# OSSI-1_LED_Panel.net
KiCad netlist of a schematic drawn in EAGLE
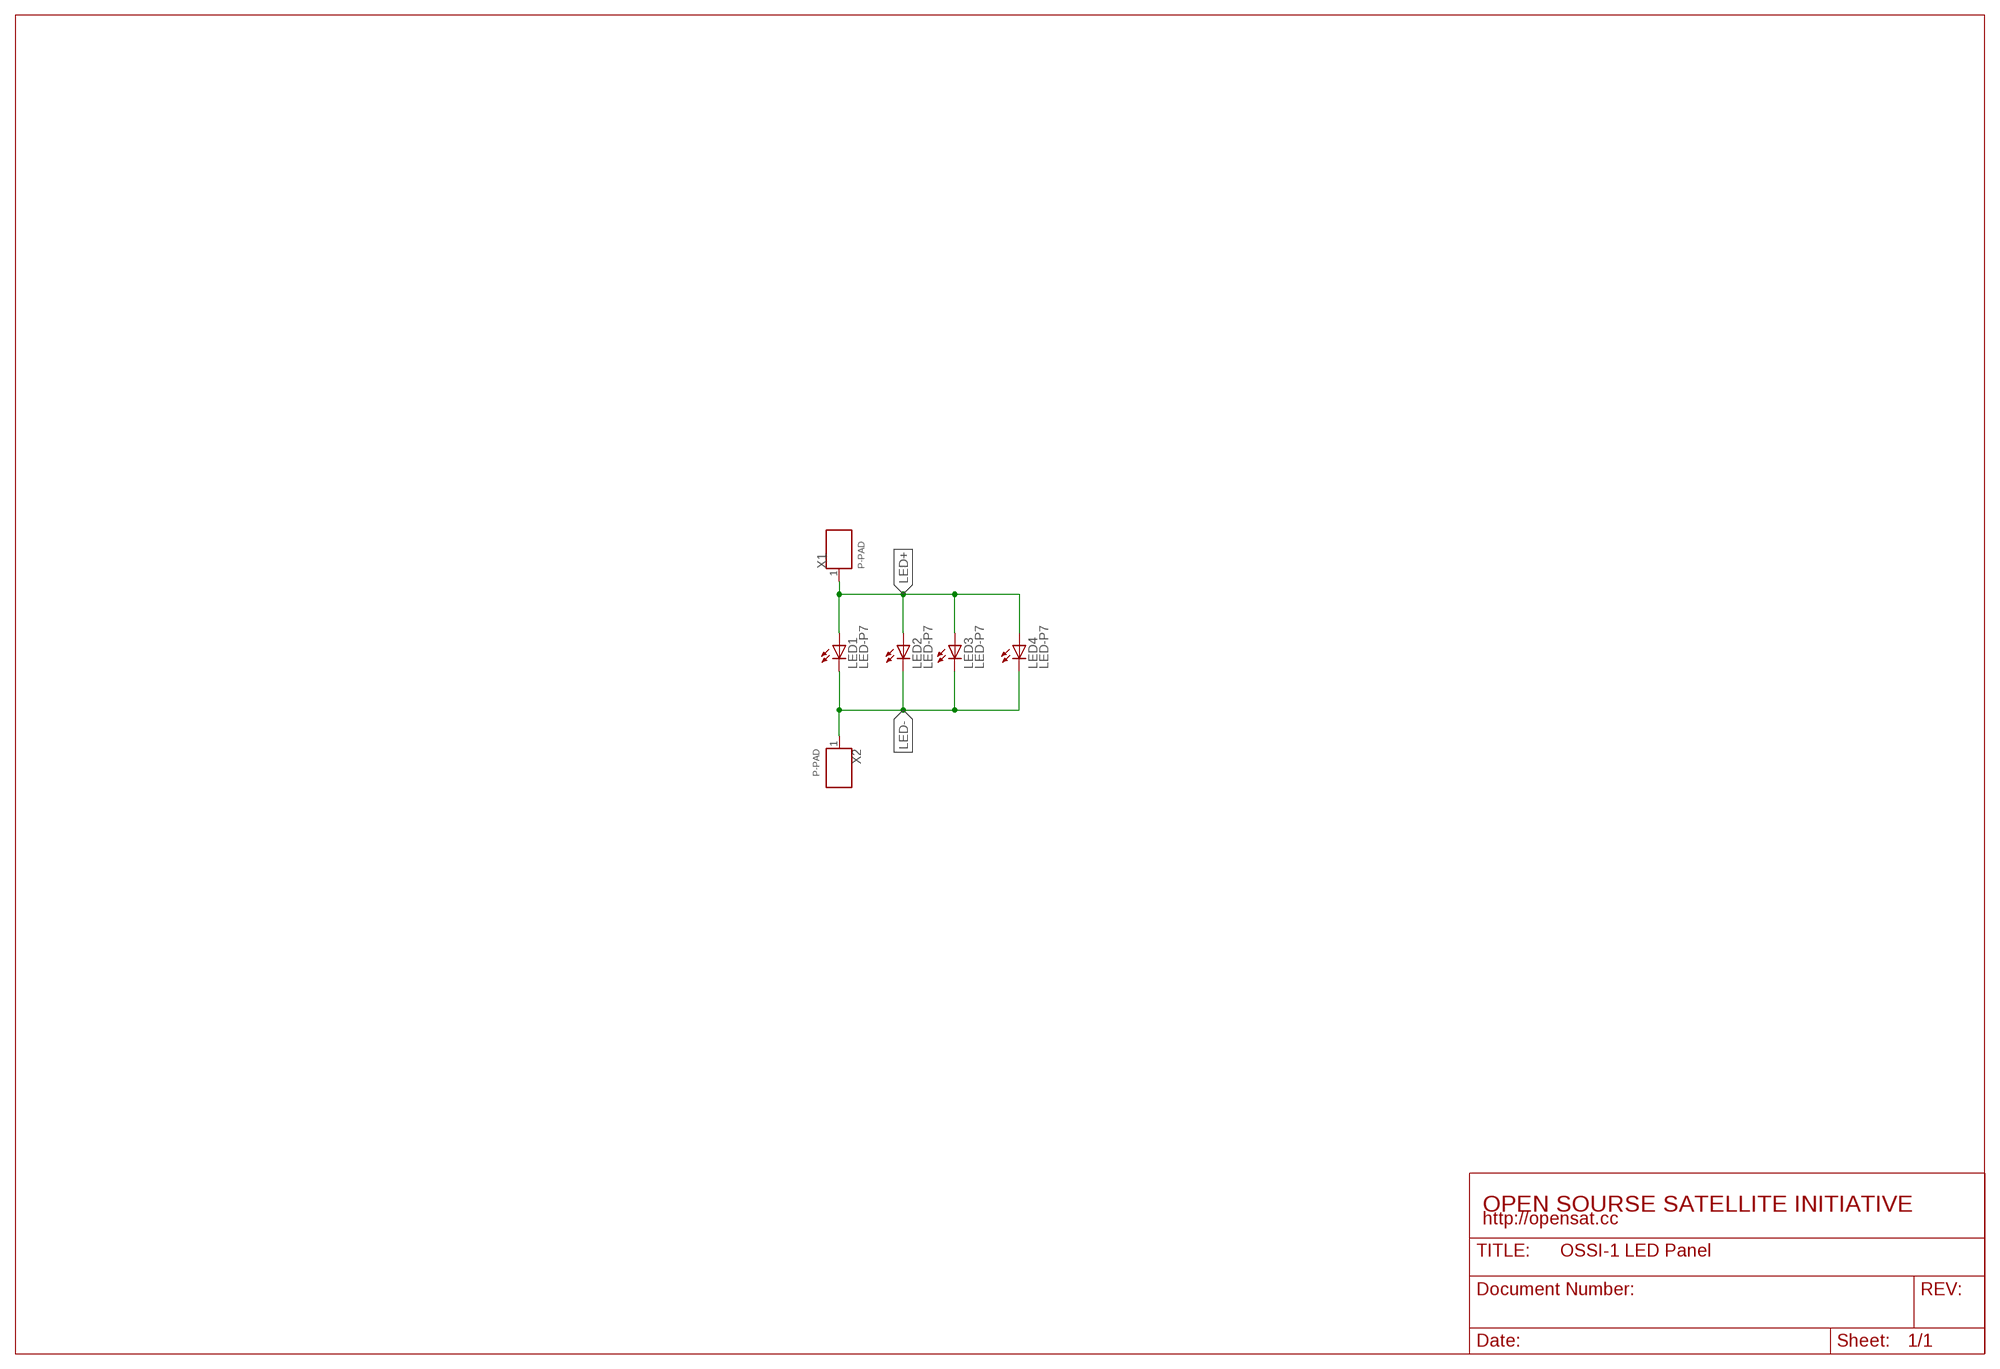
[diagram p0: schematic, sheet 1]

(export (version "E")
  (design (tool "Eeschema 10.0.6"))
  (components
    (comp (ref "LED1")
      (value "LED-P7")
      (footprint "eagle-import:P7")
      (libsource (lib "eagle-import") (part "LED-P7"))
    )
    (comp (ref "LED2")
      (value "LED-P7")
      (footprint "eagle-import:P7")
      (libsource (lib "eagle-import") (part "LED-P7"))
    )
    (comp (ref "LED3")
      (value "LED-P7")
      (footprint "eagle-import:P7")
      (libsource (lib "eagle-import") (part "LED-P7"))
    )
    (comp (ref "LED4")
      (value "LED-P7")
      (footprint "eagle-import:P7")
      (libsource (lib "eagle-import") (part "LED-P7"))
    )
    (comp (ref "X1")
      (value "P-PAD")
      (footprint "eagle-import:P-PAD")
      (libsource (lib "eagle-import") (part "P-PAD"))
    )
    (comp (ref "X2")
      (value "P-PAD")
      (footprint "eagle-import:P-PAD")
      (libsource (lib "eagle-import") (part "P-PAD"))
    )
  )
  (nets
    (net (code "1") (name "LED+") (class "Default")
      (node (ref "LED1") (pin "A") (pinfunction "A_A") (pintype "passive"))
      (node (ref "LED2") (pin "A") (pinfunction "A_A") (pintype "passive"))
      (node (ref "LED3") (pin "A") (pinfunction "A_A") (pintype "passive"))
      (node (ref "LED4") (pin "A") (pinfunction "A_A") (pintype "passive"))
      (node (ref "X1") (pin "1") (pinfunction "P$1_1") (pintype "bidirectional"))
    )
    (net (code "2") (name "LED-") (class "Default")
      (node (ref "LED1") (pin "C") (pinfunction "C_C") (pintype "passive"))
      (node (ref "LED2") (pin "C") (pinfunction "C_C") (pintype "passive"))
      (node (ref "LED3") (pin "C") (pinfunction "C_C") (pintype "passive"))
      (node (ref "LED4") (pin "C") (pinfunction "C_C") (pintype "passive"))
      (node (ref "X2") (pin "1") (pinfunction "P$1_1") (pintype "bidirectional"))
    )
  )
)
